# I2C-8574.net
KiCad netlist of a schematic drawn in EAGLE
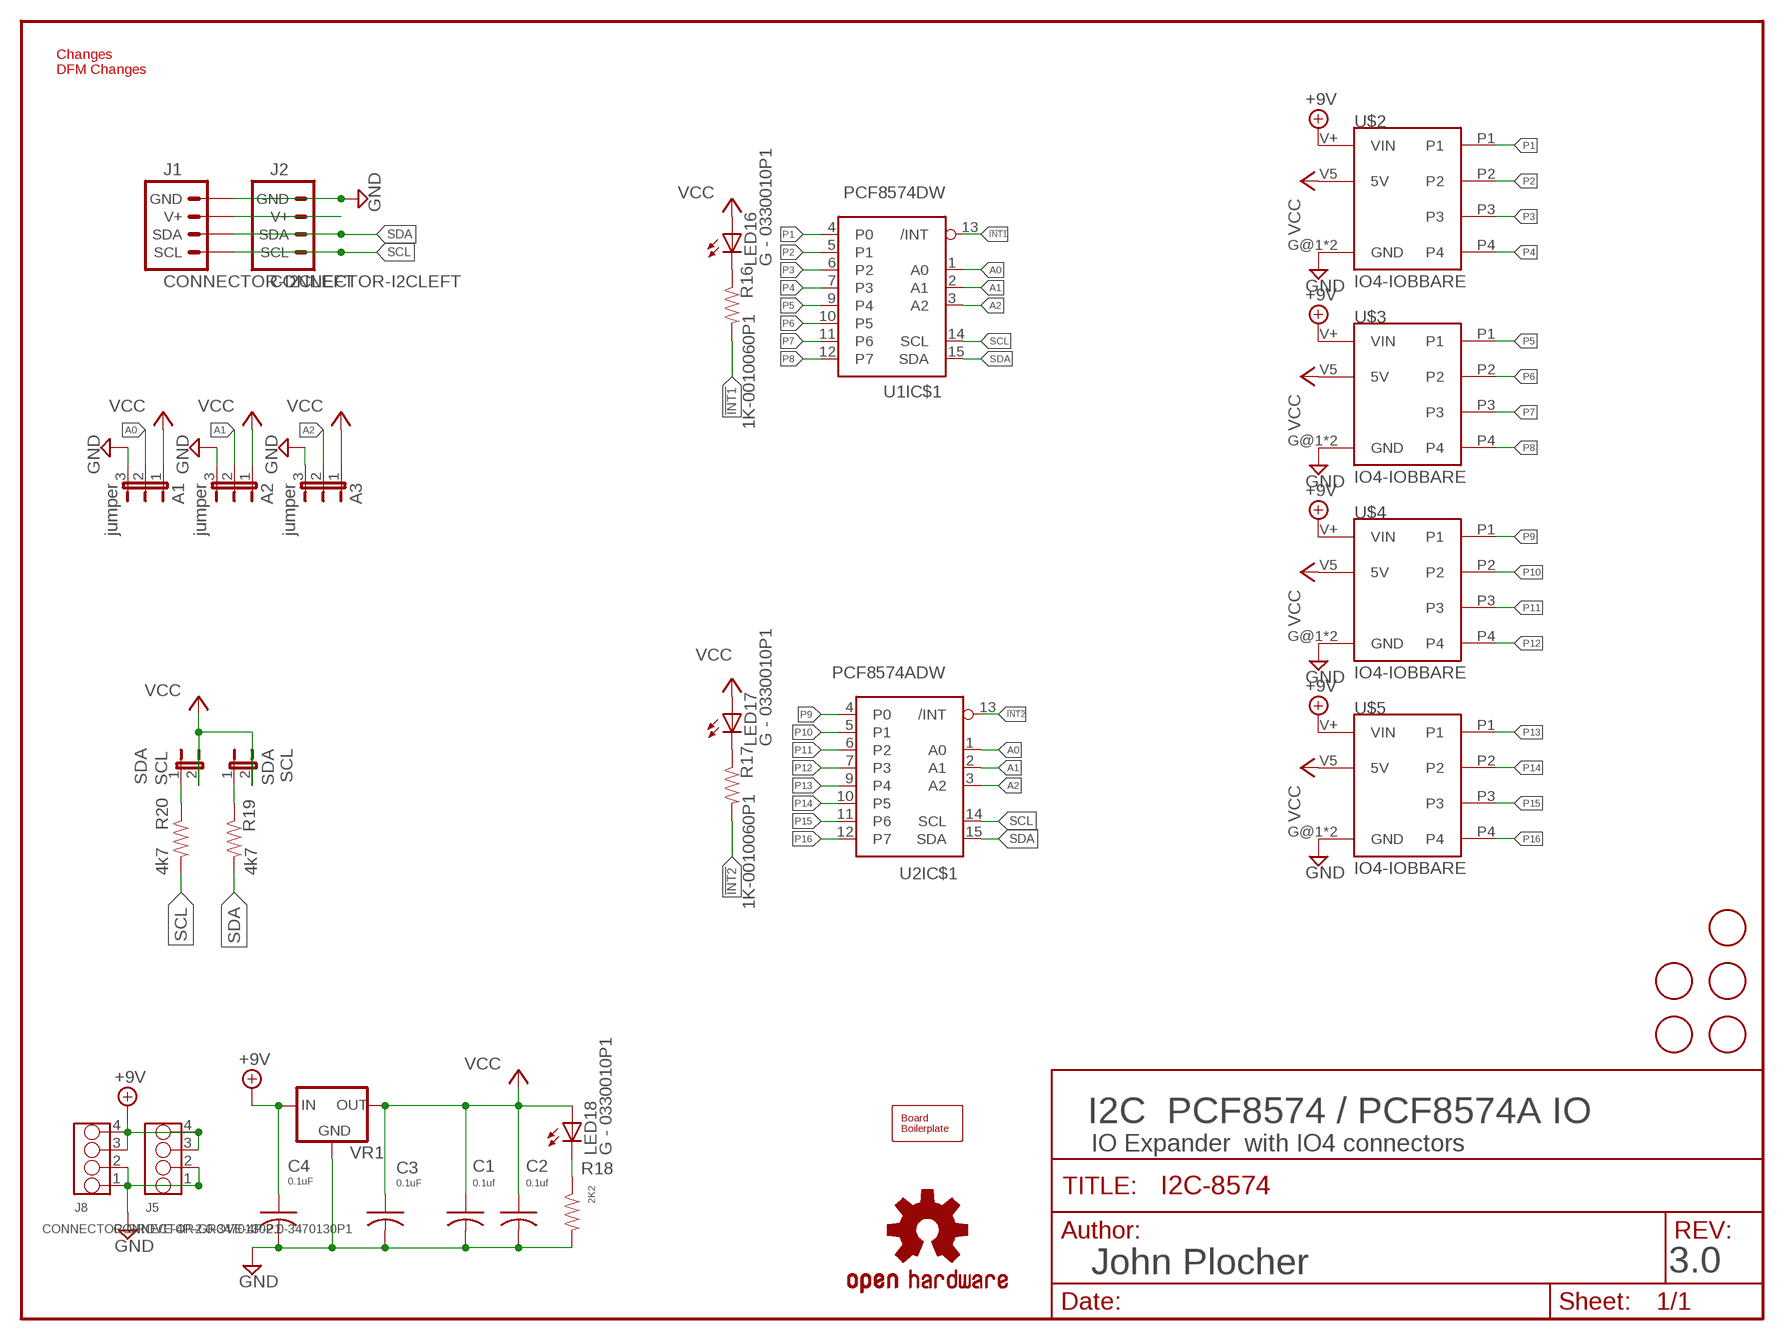
[diagram p0: schematic, sheet 1]

(export (version "E")
  (design (tool "Eeschema 10.0.6"))
  (components
    (comp (ref "A1")
      (value "jumper")
      (footprint "eagle-import:1X03")
      (libsource (lib "eagle-import") (part "JUMPER-3PTH-LOCK"))
    )
    (comp (ref "A2")
      (value "jumper")
      (footprint "eagle-import:1X03")
      (libsource (lib "eagle-import") (part "JUMPER-3PTH-LOCK"))
    )
    (comp (ref "A3")
      (value "jumper")
      (footprint "eagle-import:1X03")
      (libsource (lib "eagle-import") (part "JUMPER-3PTH-LOCK"))
    )
    (comp (ref "BOARD1")
      (value "BOARD80X100-NOHOLES")
      (footprint "eagle-import:BOARD-DINRAIL-3.17IN-NOHOLES")
      (libsource (lib "eagle-import") (part "BOARD80X100-NOHOLES"))
    )
    (comp (ref "C1")
      (value "0.1uf")
      (footprint "eagle-import:0805-CAP")
      (libsource (lib "eagle-import") (part "C0805"))
    )
    (comp (ref "C2")
      (value "0.1uf")
      (footprint "eagle-import:0805-CAP")
      (libsource (lib "eagle-import") (part "C0805"))
    )
    (comp (ref "C3")
      (value "0.1uF")
      (footprint "eagle-import:0805-CAP")
      (libsource (lib "eagle-import") (part "C0805"))
    )
    (comp (ref "C4")
      (value "0.1uF")
      (footprint "eagle-import:0805-CAP")
      (libsource (lib "eagle-import") (part "C0805"))
    )
    (comp (ref "FID-U1")
      (value "FIDUCIAL")
      (footprint "eagle-import:FIDUCIAL_1MM")
      (libsource (lib "eagle-import") (part "FIDUCIAL"))
    )
    (comp (ref "FID-U2")
      (value "FIDUCIAL")
      (footprint "eagle-import:FIDUCIAL_1MM")
      (libsource (lib "eagle-import") (part "FIDUCIAL"))
    )
    (comp (ref "FID1")
      (value "FIDUCIAL")
      (footprint "eagle-import:FIDUCIAL_1MM")
      (libsource (lib "eagle-import") (part "FIDUCIAL"))
    )
    (comp (ref "FID2")
      (value "FIDUCIAL")
      (footprint "eagle-import:FIDUCIAL_1MM")
      (libsource (lib "eagle-import") (part "FIDUCIAL"))
    )
    (comp (ref "FID3")
      (value "FIDUCIAL")
      (footprint "eagle-import:FIDUCIAL_1MM")
      (libsource (lib "eagle-import") (part "FIDUCIAL"))
    )
    (comp (ref "J1")
      (value "CONNECTOR-I2CLEFT")
      (footprint "eagle-import:I2C-L")
      (libsource (lib "eagle-import") (part "CONNECTOR-I2CLEFT"))
    )
    (comp (ref "J2")
      (value "CONNECTOR-I2CLEFT")
      (footprint "eagle-import:I2C-L")
      (libsource (lib "eagle-import") (part "CONNECTOR-I2CLEFT"))
    )
    (comp (ref "J5")
      (value "CONNECTOR-GROVE-4P-2.0-3470130P1")
      (footprint "eagle-import:4P-2.0")
      (libsource (lib "eagle-import") (part "CONNECTOR-GROVE-4P-2.0-3470130P1"))
    )
    (comp (ref "J8")
      (value "CONNECTOR-GROVE-4P-2.0-3470130P1")
      (footprint "eagle-import:4P-2.0")
      (libsource (lib "eagle-import") (part "CONNECTOR-GROVE-4P-2.0-3470130P1"))
    )
    (comp (ref "LED16")
      (value "G - 0330010P1")
      (footprint "eagle-import:0603-LED")
      (libsource (lib "eagle-import") (part "LED0603-LED"))
    )
    (comp (ref "LED17")
      (value "G - 0330010P1")
      (footprint "eagle-import:0603-LED")
      (libsource (lib "eagle-import") (part "LED0603-LED"))
    )
    (comp (ref "LED18")
      (value "G - 0330010P1")
      (footprint "eagle-import:0603-LED")
      (libsource (lib "eagle-import") (part "LED0603-LED"))
    )
    (comp (ref "R16")
      (value "1K-0010060P1")
      (footprint "eagle-import:0805-RES")
      (libsource (lib "eagle-import") (part "SPCoast-minimal_R0805-RES"))
    )
    (comp (ref "R17")
      (value "1K-0010060P1")
      (footprint "eagle-import:0805-RES")
      (libsource (lib "eagle-import") (part "SPCoast-minimal_R0805-RES"))
    )
    (comp (ref "R18")
      (value "2K2")
      (footprint "eagle-import:0805-RES")
      (libsource (lib "eagle-import") (part "SPCoast-minimal_R0805-RES"))
    )
    (comp (ref "R19")
      (value "4k7")
      (footprint "eagle-import:0805-RES")
      (libsource (lib "eagle-import") (part "R0805-RES"))
    )
    (comp (ref "R20")
      (value "4k7")
      (footprint "eagle-import:0805-RES")
      (libsource (lib "eagle-import") (part "R0805-RES"))
    )
    (comp (ref "SCL")
      (value "SDA")
      (footprint "eagle-import:1X02_LOCK")
      (libsource (lib "eagle-import") (part "JUMPER-2PTH_LOCK"))
    )
    (comp (ref "SDA")
      (value "SCL")
      (footprint "eagle-import:1X02_LOCK")
      (libsource (lib "eagle-import") (part "JUMPER-2PTH_LOCK"))
    )
    (comp (ref "U$1")
      (value "OSHW-LOGOL")
      (footprint "eagle-import:OSHW-LOGO-L")
      (libsource (lib "eagle-import") (part "OSHW-LOGOL"))
    )
    (comp (ref "U$2")
      (value "IO4-IOBBARE")
      (footprint "eagle-import:IO4-IOB")
      (libsource (lib "eagle-import") (part "IO4-IOBBARE"))
    )
    (comp (ref "U$3")
      (value "IO4-IOBBARE")
      (footprint "eagle-import:IO4-IOB")
      (libsource (lib "eagle-import") (part "IO4-IOBBARE"))
    )
    (comp (ref "U$4")
      (value "IO4-IOBBARE")
      (footprint "eagle-import:IO4-IOB")
      (libsource (lib "eagle-import") (part "IO4-IOBBARE"))
    )
    (comp (ref "U$5")
      (value "IO4-IOBBARE")
      (footprint "eagle-import:IO4-IOB")
      (libsource (lib "eagle-import") (part "IO4-IOBBARE"))
    )
    (comp (ref "U1")
      (value "PCF8574DW")
      (footprint "eagle-import:SO-16DW")
      (libsource (lib "eagle-import") (part "PCF8574DW"))
    )
    (comp (ref "U2")
      (value "PCF8574ADW")
      (footprint "eagle-import:SO-16DW")
      (libsource (lib "eagle-import") (part "PCF8574ADW"))
    )
    (comp (ref "VR1")
      (value "VREG-DPAK-5")
      (footprint "eagle-import:TO-252")
      (libsource (lib "eagle-import") (part "VREG-?-DPAK5"))
    )
  )
  (nets
    (net (code "1") (name "+9V") (class "Default")
      (node (ref "C4") (pin "1") (pinfunction "1_1") (pintype "passive"))
      (node (ref "J5") (pin "3") (pinfunction "3_3") (pintype "bidirectional"))
      (node (ref "J5") (pin "4") (pinfunction "4_4") (pintype "bidirectional"))
      (node (ref "J8") (pin "3") (pinfunction "3_3") (pintype "bidirectional"))
      (node (ref "J8") (pin "4") (pinfunction "4_4") (pintype "bidirectional"))
      (node (ref "U$2") (pin "V+") (pinfunction "VIN_V+") (pintype "power_in"))
      (node (ref "U$3") (pin "V+") (pinfunction "VIN_V+") (pintype "power_in"))
      (node (ref "U$4") (pin "V+") (pinfunction "VIN_V+") (pintype "power_in"))
      (node (ref "U$5") (pin "V+") (pinfunction "VIN_V+") (pintype "power_in"))
      (node (ref "VR1") (pin "1") (pinfunction "IN_1") (pintype "input"))
    )
    (net (code "2") (name "/~{INT1}") (class "Default")
      (node (ref "R16") (pin "2") (pinfunction "2_2") (pintype "passive"))
      (node (ref "U1") (pin "13") (pinfunction "/INT_13") (pintype "output"))
    )
    (net (code "3") (name "/~{INT2}") (class "Default")
      (node (ref "R17") (pin "2") (pinfunction "2_2") (pintype "passive"))
      (node (ref "U2") (pin "13") (pinfunction "/INT_13") (pintype "output"))
    )
    (net (code "4") (name "A0") (class "Default")
      (node (ref "A1") (pin "2") (pinfunction "2_2") (pintype "passive"))
      (node (ref "U1") (pin "1") (pinfunction "A0_1") (pintype "input"))
      (node (ref "U2") (pin "1") (pinfunction "A0_1") (pintype "input"))
    )
    (net (code "5") (name "A1") (class "Default")
      (node (ref "A2") (pin "2") (pinfunction "2_2") (pintype "passive"))
      (node (ref "U1") (pin "2") (pinfunction "A1_2") (pintype "input"))
      (node (ref "U2") (pin "2") (pinfunction "A1_2") (pintype "input"))
    )
    (net (code "6") (name "A2") (class "Default")
      (node (ref "A3") (pin "2") (pinfunction "2_2") (pintype "passive"))
      (node (ref "U1") (pin "3") (pinfunction "A2_3") (pintype "input"))
      (node (ref "U2") (pin "3") (pinfunction "A2_3") (pintype "input"))
    )
    (net (code "7") (name "GND") (class "Default")
      (node (ref "A1") (pin "3") (pinfunction "3_3") (pintype "passive"))
      (node (ref "A2") (pin "3") (pinfunction "3_3") (pintype "passive"))
      (node (ref "A3") (pin "3") (pinfunction "3_3") (pintype "passive"))
      (node (ref "C1") (pin "2") (pinfunction "2_2") (pintype "passive"))
      (node (ref "C2") (pin "2") (pinfunction "2_2") (pintype "passive"))
      (node (ref "C3") (pin "2") (pinfunction "2_2") (pintype "passive"))
      (node (ref "C4") (pin "2") (pinfunction "2_2") (pintype "passive"))
      (node (ref "J1") (pin "GND") (pinfunction "GND_GND") (pintype "passive"))
      (node (ref "J1") (pin "GND@1") (pinfunction "GND_GND@1") (pintype "passive"))
      (node (ref "J2") (pin "GND") (pinfunction "GND_GND") (pintype "passive"))
      (node (ref "J2") (pin "GND@1") (pinfunction "GND_GND@1") (pintype "passive"))
      (node (ref "J5") (pin "1") (pinfunction "1_1") (pintype "bidirectional"))
      (node (ref "J5") (pin "2") (pinfunction "2_2") (pintype "bidirectional"))
      (node (ref "J8") (pin "1") (pinfunction "1_1") (pintype "bidirectional"))
      (node (ref "J8") (pin "2") (pinfunction "2_2") (pintype "bidirectional"))
      (node (ref "R18") (pin "2") (pinfunction "2_2") (pintype "passive"))
      (node (ref "U$2") (pin "G@1") (pinfunction "GND_G@1") (pintype "power_in"))
      (node (ref "U$2") (pin "G@2") (pinfunction "GND_G@2") (pintype "power_in"))
      (node (ref "U$3") (pin "G@1") (pinfunction "GND_G@1") (pintype "power_in"))
      (node (ref "U$3") (pin "G@2") (pinfunction "GND_G@2") (pintype "power_in"))
      (node (ref "U$4") (pin "G@1") (pinfunction "GND_G@1") (pintype "power_in"))
      (node (ref "U$4") (pin "G@2") (pinfunction "GND_G@2") (pintype "power_in"))
      (node (ref "U$5") (pin "G@1") (pinfunction "GND_G@1") (pintype "power_in"))
      (node (ref "U$5") (pin "G@2") (pinfunction "GND_G@2") (pintype "power_in"))
      (node (ref "VR1") (pin "2") (pinfunction "GND_2") (pintype "input"))
    )
    (net (code "8") (name "Net-(J1-PadV+)") (class "Default")
      (node (ref "J1") (pin "V+") (pinfunction "V+_V+") (pintype "passive"))
      (node (ref "J1") (pin "V+@1") (pinfunction "V+_V+@1") (pintype "passive"))
      (node (ref "J2") (pin "V+") (pinfunction "V+_V+") (pintype "passive"))
      (node (ref "J2") (pin "V+@1") (pinfunction "V+_V+@1") (pintype "passive"))
    )
    (net (code "9") (name "Net-(LED16-PadC)") (class "Default")
      (node (ref "LED16") (pin "C") (pinfunction "C_C") (pintype "passive"))
      (node (ref "R16") (pin "1") (pinfunction "1_1") (pintype "passive"))
    )
    (net (code "10") (name "Net-(LED17-PadC)") (class "Default")
      (node (ref "LED17") (pin "C") (pinfunction "C_C") (pintype "passive"))
      (node (ref "R17") (pin "1") (pinfunction "1_1") (pintype "passive"))
    )
    (net (code "11") (name "Net-(LED18-PadC)") (class "Default")
      (node (ref "LED18") (pin "C") (pinfunction "C_C") (pintype "passive"))
      (node (ref "R18") (pin "1") (pinfunction "1_1") (pintype "passive"))
    )
    (net (code "12") (name "Net-(R19-Pad1)") (class "Default")
      (node (ref "R19") (pin "1") (pinfunction "1_1") (pintype "passive"))
      (node (ref "SCL") (pin "1") (pinfunction "1_1") (pintype "passive"))
    )
    (net (code "13") (name "Net-(R20-Pad1)") (class "Default")
      (node (ref "R20") (pin "1") (pinfunction "1_1") (pintype "passive"))
      (node (ref "SDA") (pin "1") (pinfunction "1_1") (pintype "passive"))
    )
    (net (code "14") (name "P1") (class "Default")
      (node (ref "U$2") (pin "P1") (pinfunction "P1_P1") (pintype "bidirectional"))
      (node (ref "U1") (pin "4") (pinfunction "P0_4") (pintype "bidirectional"))
    )
    (net (code "15") (name "P2") (class "Default")
      (node (ref "U$2") (pin "P2") (pinfunction "P2_P2") (pintype "bidirectional"))
      (node (ref "U1") (pin "5") (pinfunction "P1_5") (pintype "bidirectional"))
    )
    (net (code "16") (name "P3") (class "Default")
      (node (ref "U$2") (pin "P3") (pinfunction "P3_P3") (pintype "bidirectional"))
      (node (ref "U1") (pin "6") (pinfunction "P2_6") (pintype "bidirectional"))
    )
    (net (code "17") (name "P4") (class "Default")
      (node (ref "U$2") (pin "P4") (pinfunction "P4_P4") (pintype "bidirectional"))
      (node (ref "U1") (pin "7") (pinfunction "P3_7") (pintype "bidirectional"))
    )
    (net (code "18") (name "P5") (class "Default")
      (node (ref "U$3") (pin "P1") (pinfunction "P1_P1") (pintype "bidirectional"))
      (node (ref "U1") (pin "9") (pinfunction "P4_9") (pintype "bidirectional"))
    )
    (net (code "19") (name "P6") (class "Default")
      (node (ref "U$3") (pin "P2") (pinfunction "P2_P2") (pintype "bidirectional"))
      (node (ref "U1") (pin "10") (pinfunction "P5_10") (pintype "bidirectional"))
    )
    (net (code "20") (name "P7") (class "Default")
      (node (ref "U$3") (pin "P3") (pinfunction "P3_P3") (pintype "bidirectional"))
      (node (ref "U1") (pin "11") (pinfunction "P6_11") (pintype "bidirectional"))
    )
    (net (code "21") (name "P8") (class "Default")
      (node (ref "U$3") (pin "P4") (pinfunction "P4_P4") (pintype "bidirectional"))
      (node (ref "U1") (pin "12") (pinfunction "P7_12") (pintype "bidirectional"))
    )
    (net (code "22") (name "P9") (class "Default")
      (node (ref "U$4") (pin "P1") (pinfunction "P1_P1") (pintype "bidirectional"))
      (node (ref "U2") (pin "4") (pinfunction "P0_4") (pintype "bidirectional"))
    )
    (net (code "23") (name "P10") (class "Default")
      (node (ref "U$4") (pin "P2") (pinfunction "P2_P2") (pintype "bidirectional"))
      (node (ref "U2") (pin "5") (pinfunction "P1_5") (pintype "bidirectional"))
    )
    (net (code "24") (name "P11") (class "Default")
      (node (ref "U$4") (pin "P3") (pinfunction "P3_P3") (pintype "bidirectional"))
      (node (ref "U2") (pin "6") (pinfunction "P2_6") (pintype "bidirectional"))
    )
    (net (code "25") (name "P12") (class "Default")
      (node (ref "U$4") (pin "P4") (pinfunction "P4_P4") (pintype "bidirectional"))
      (node (ref "U2") (pin "7") (pinfunction "P3_7") (pintype "bidirectional"))
    )
    (net (code "26") (name "P13") (class "Default")
      (node (ref "U$5") (pin "P1") (pinfunction "P1_P1") (pintype "bidirectional"))
      (node (ref "U2") (pin "9") (pinfunction "P4_9") (pintype "bidirectional"))
    )
    (net (code "27") (name "P14") (class "Default")
      (node (ref "U$5") (pin "P2") (pinfunction "P2_P2") (pintype "bidirectional"))
      (node (ref "U2") (pin "10") (pinfunction "P5_10") (pintype "bidirectional"))
    )
    (net (code "28") (name "P15") (class "Default")
      (node (ref "U$5") (pin "P3") (pinfunction "P3_P3") (pintype "bidirectional"))
      (node (ref "U2") (pin "11") (pinfunction "P6_11") (pintype "bidirectional"))
    )
    (net (code "29") (name "P16") (class "Default")
      (node (ref "U$5") (pin "P4") (pinfunction "P4_P4") (pintype "bidirectional"))
      (node (ref "U2") (pin "12") (pinfunction "P7_12") (pintype "bidirectional"))
    )
    (net (code "30") (name "SCL") (class "Default")
      (node (ref "J1") (pin "SCL") (pinfunction "SCL_SCL") (pintype "passive"))
      (node (ref "J1") (pin "SCL@1") (pinfunction "SCL_SCL@1") (pintype "passive"))
      (node (ref "J2") (pin "SCL") (pinfunction "SCL_SCL") (pintype "passive"))
      (node (ref "J2") (pin "SCL@1") (pinfunction "SCL_SCL@1") (pintype "passive"))
      (node (ref "R20") (pin "2") (pinfunction "2_2") (pintype "passive"))
      (node (ref "U1") (pin "14") (pinfunction "SCL_14") (pintype "input"))
      (node (ref "U2") (pin "14") (pinfunction "SCL_14") (pintype "input"))
    )
    (net (code "31") (name "SDA") (class "Default")
      (node (ref "J1") (pin "SDA") (pinfunction "SDA_SDA") (pintype "passive"))
      (node (ref "J1") (pin "SDA@1") (pinfunction "SDA_SDA@1") (pintype "passive"))
      (node (ref "J2") (pin "SDA") (pinfunction "SDA_SDA") (pintype "passive"))
      (node (ref "J2") (pin "SDA@1") (pinfunction "SDA_SDA@1") (pintype "passive"))
      (node (ref "R19") (pin "2") (pinfunction "2_2") (pintype "passive"))
      (node (ref "U1") (pin "15") (pinfunction "SDA_15") (pintype "bidirectional"))
      (node (ref "U2") (pin "15") (pinfunction "SDA_15") (pintype "bidirectional"))
    )
    (net (code "32") (name "VCC") (class "Default")
      (node (ref "A1") (pin "1") (pinfunction "1_1") (pintype "passive"))
      (node (ref "A2") (pin "1") (pinfunction "1_1") (pintype "passive"))
      (node (ref "A3") (pin "1") (pinfunction "1_1") (pintype "passive"))
      (node (ref "C1") (pin "1") (pinfunction "1_1") (pintype "passive"))
      (node (ref "C2") (pin "1") (pinfunction "1_1") (pintype "passive"))
      (node (ref "C3") (pin "1") (pinfunction "1_1") (pintype "passive"))
      (node (ref "LED16") (pin "A") (pinfunction "A_A") (pintype "passive"))
      (node (ref "LED17") (pin "A") (pinfunction "A_A") (pintype "passive"))
      (node (ref "LED18") (pin "A") (pinfunction "A_A") (pintype "passive"))
      (node (ref "SCL") (pin "2") (pinfunction "2_2") (pintype "passive"))
      (node (ref "SDA") (pin "2") (pinfunction "2_2") (pintype "passive"))
      (node (ref "U$2") (pin "V5") (pinfunction "5V_V5") (pintype "power_in"))
      (node (ref "U$3") (pin "V5") (pinfunction "5V_V5") (pintype "power_in"))
      (node (ref "U$4") (pin "V5") (pinfunction "5V_V5") (pintype "power_in"))
      (node (ref "U$5") (pin "V5") (pinfunction "5V_V5") (pintype "power_in"))
      (node (ref "VR1") (pin "3") (pinfunction "OUT_3") (pintype "output"))
    )
  )
)
